# NeoDigito_Big_V2_1_PCBWay.net
KiCad netlist of a schematic drawn in EAGLE
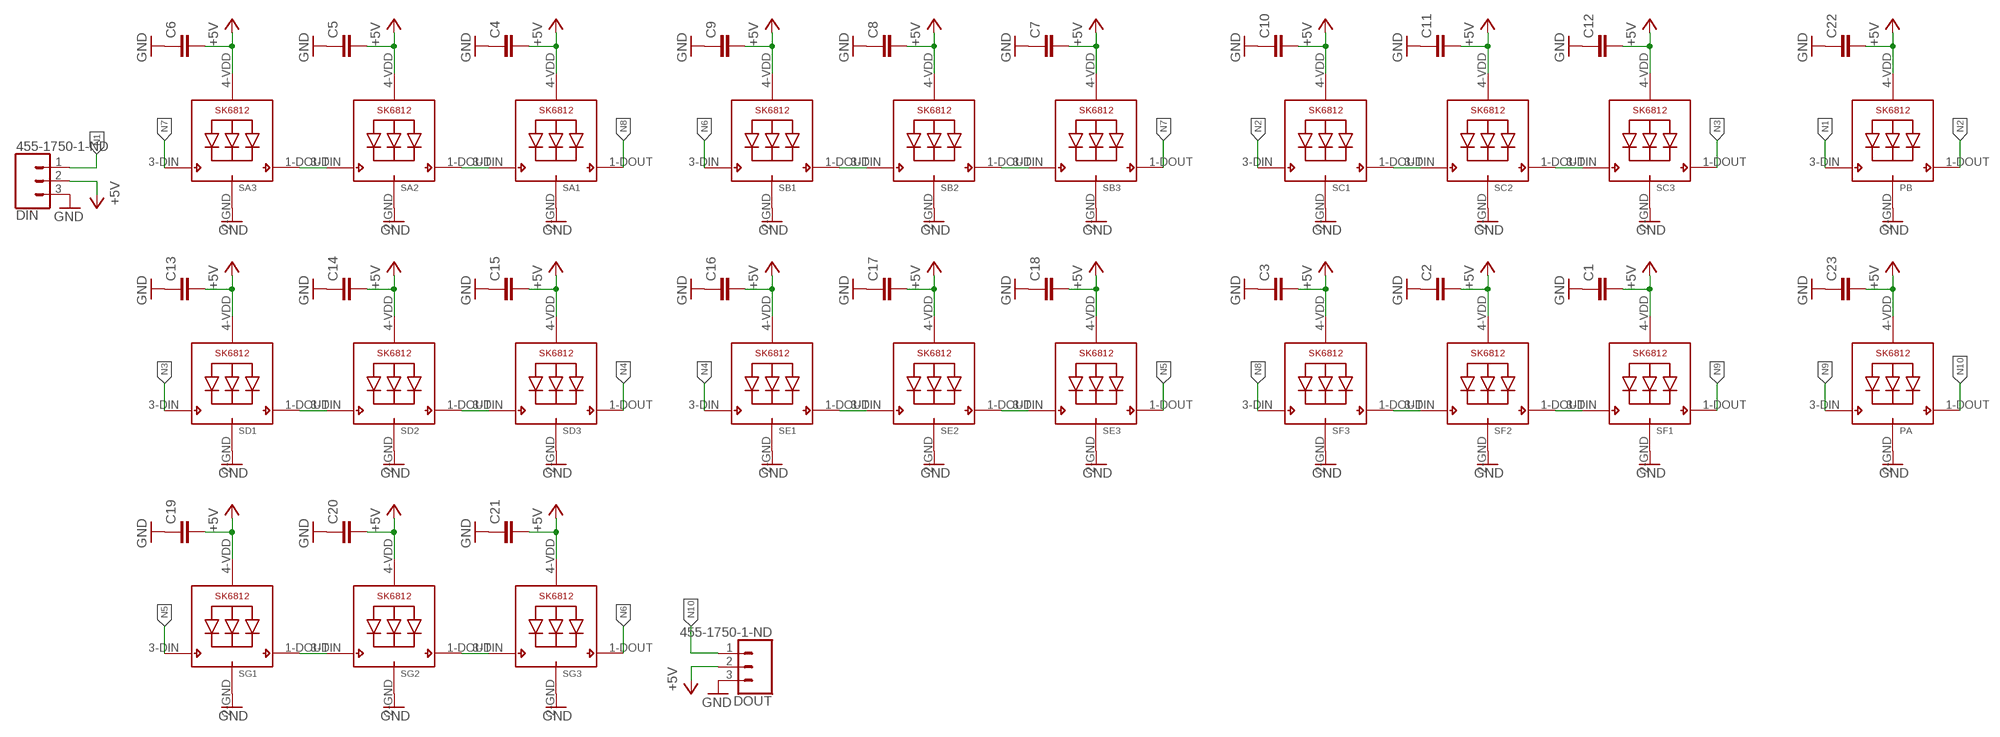
[diagram p0: schematic, sheet 1]

(export (version "E")
  (design (tool "Eeschema 10.0.6"))
  (components
    (comp (ref "C1")
      (value "C-EUC0805")
      (footprint "eagle-import:C0805")
      (libsource (lib "eagle-import") (part "C-EUC0805"))
    )
    (comp (ref "C2")
      (value "C-EUC0805")
      (footprint "eagle-import:C0805")
      (libsource (lib "eagle-import") (part "C-EUC0805"))
    )
    (comp (ref "C3")
      (value "C-EUC0805")
      (footprint "eagle-import:C0805")
      (libsource (lib "eagle-import") (part "C-EUC0805"))
    )
    (comp (ref "C4")
      (value "C-EUC0805")
      (footprint "eagle-import:C0805")
      (libsource (lib "eagle-import") (part "C-EUC0805"))
    )
    (comp (ref "C5")
      (value "C-EUC0805")
      (footprint "eagle-import:C0805")
      (libsource (lib "eagle-import") (part "C-EUC0805"))
    )
    (comp (ref "C6")
      (value "C-EUC0805")
      (footprint "eagle-import:C0805")
      (libsource (lib "eagle-import") (part "C-EUC0805"))
    )
    (comp (ref "C7")
      (value "C-EUC0805")
      (footprint "eagle-import:C0805")
      (libsource (lib "eagle-import") (part "C-EUC0805"))
    )
    (comp (ref "C8")
      (value "C-EUC0805")
      (footprint "eagle-import:C0805")
      (libsource (lib "eagle-import") (part "C-EUC0805"))
    )
    (comp (ref "C9")
      (value "C-EUC0805")
      (footprint "eagle-import:C0805")
      (libsource (lib "eagle-import") (part "C-EUC0805"))
    )
    (comp (ref "C10")
      (value "C-EUC0805")
      (footprint "eagle-import:C0805")
      (libsource (lib "eagle-import") (part "C-EUC0805"))
    )
    (comp (ref "C11")
      (value "C-EUC0805")
      (footprint "eagle-import:C0805")
      (libsource (lib "eagle-import") (part "C-EUC0805"))
    )
    (comp (ref "C12")
      (value "C-EUC0805")
      (footprint "eagle-import:C0805")
      (libsource (lib "eagle-import") (part "C-EUC0805"))
    )
    (comp (ref "C13")
      (value "C-EUC0805")
      (footprint "eagle-import:C0805")
      (libsource (lib "eagle-import") (part "C-EUC0805"))
    )
    (comp (ref "C14")
      (value "C-EUC0805")
      (footprint "eagle-import:C0805")
      (libsource (lib "eagle-import") (part "C-EUC0805"))
    )
    (comp (ref "C15")
      (value "C-EUC0805")
      (footprint "eagle-import:C0805")
      (libsource (lib "eagle-import") (part "C-EUC0805"))
    )
    (comp (ref "C16")
      (value "C-EUC0805")
      (footprint "eagle-import:C0805")
      (libsource (lib "eagle-import") (part "C-EUC0805"))
    )
    (comp (ref "C17")
      (value "C-EUC0805")
      (footprint "eagle-import:C0805")
      (libsource (lib "eagle-import") (part "C-EUC0805"))
    )
    (comp (ref "C18")
      (value "C-EUC0805")
      (footprint "eagle-import:C0805")
      (libsource (lib "eagle-import") (part "C-EUC0805"))
    )
    (comp (ref "C19")
      (value "C-EUC0805")
      (footprint "eagle-import:C0805")
      (libsource (lib "eagle-import") (part "C-EUC0805"))
    )
    (comp (ref "C20")
      (value "C-EUC0805")
      (footprint "eagle-import:C0805")
      (libsource (lib "eagle-import") (part "C-EUC0805"))
    )
    (comp (ref "C21")
      (value "C-EUC0805")
      (footprint "eagle-import:C0805")
      (libsource (lib "eagle-import") (part "C-EUC0805"))
    )
    (comp (ref "C22")
      (value "C-EUC0805")
      (footprint "eagle-import:C0805")
      (libsource (lib "eagle-import") (part "C-EUC0805"))
    )
    (comp (ref "C23")
      (value "C-EUC0805")
      (footprint "eagle-import:C0805")
      (libsource (lib "eagle-import") (part "C-EUC0805"))
    )
    (comp (ref "DIN")
      (value "455-1750-1-ND")
      (footprint "eagle-import:1X03")
      (libsource (lib "eagle-import") (part "CONN_03"))
    )
    (comp (ref "DOUT")
      (value "455-1750-1-ND")
      (footprint "eagle-import:1X03_NO_SILK")
      (libsource (lib "eagle-import") (part "CONN_031X03_NO_SILK"))
    )
    (comp (ref "PA")
      (value "SK6812_3535")
      (footprint "eagle-import:LED3535")
      (libsource (lib "eagle-import") (part "SK6812_3535"))
    )
    (comp (ref "PB")
      (value "SK6812_3535")
      (footprint "eagle-import:LED3535")
      (libsource (lib "eagle-import") (part "SK6812_3535"))
    )
    (comp (ref "SA1")
      (value "SK6812_3535")
      (footprint "eagle-import:LED3535")
      (libsource (lib "eagle-import") (part "SK6812_3535"))
    )
    (comp (ref "SA2")
      (value "SK6812_3535")
      (footprint "eagle-import:LED3535")
      (libsource (lib "eagle-import") (part "SK6812_3535"))
    )
    (comp (ref "SA3")
      (value "SK6812_3535")
      (footprint "eagle-import:LED3535")
      (libsource (lib "eagle-import") (part "SK6812_3535"))
    )
    (comp (ref "SB1")
      (value "SK6812_3535")
      (footprint "eagle-import:LED3535")
      (libsource (lib "eagle-import") (part "SK6812_3535"))
    )
    (comp (ref "SB2")
      (value "SK6812_3535")
      (footprint "eagle-import:LED3535")
      (libsource (lib "eagle-import") (part "SK6812_3535"))
    )
    (comp (ref "SB3")
      (value "SK6812_3535")
      (footprint "eagle-import:LED3535")
      (libsource (lib "eagle-import") (part "SK6812_3535"))
    )
    (comp (ref "SC1")
      (value "SK6812_3535")
      (footprint "eagle-import:LED3535")
      (libsource (lib "eagle-import") (part "SK6812_3535"))
    )
    (comp (ref "SC2")
      (value "SK6812_3535")
      (footprint "eagle-import:LED3535")
      (libsource (lib "eagle-import") (part "SK6812_3535"))
    )
    (comp (ref "SC3")
      (value "SK6812_3535")
      (footprint "eagle-import:LED3535")
      (libsource (lib "eagle-import") (part "SK6812_3535"))
    )
    (comp (ref "SD1")
      (value "SK6812_3535")
      (footprint "eagle-import:LED3535")
      (libsource (lib "eagle-import") (part "SK6812_3535"))
    )
    (comp (ref "SD2")
      (value "SK6812_3535")
      (footprint "eagle-import:LED3535")
      (libsource (lib "eagle-import") (part "SK6812_3535"))
    )
    (comp (ref "SD3")
      (value "SK6812_3535")
      (footprint "eagle-import:LED3535")
      (libsource (lib "eagle-import") (part "SK6812_3535"))
    )
    (comp (ref "SE1")
      (value "SK6812_3535")
      (footprint "eagle-import:LED3535")
      (libsource (lib "eagle-import") (part "SK6812_3535"))
    )
    (comp (ref "SE2")
      (value "SK6812_3535")
      (footprint "eagle-import:LED3535")
      (libsource (lib "eagle-import") (part "SK6812_3535"))
    )
    (comp (ref "SE3")
      (value "SK6812_3535")
      (footprint "eagle-import:LED3535")
      (libsource (lib "eagle-import") (part "SK6812_3535"))
    )
    (comp (ref "SF1")
      (value "SK6812_3535")
      (footprint "eagle-import:LED3535")
      (libsource (lib "eagle-import") (part "SK6812_3535"))
    )
    (comp (ref "SF2")
      (value "SK6812_3535")
      (footprint "eagle-import:LED3535")
      (libsource (lib "eagle-import") (part "SK6812_3535"))
    )
    (comp (ref "SF3")
      (value "SK6812_3535")
      (footprint "eagle-import:LED3535")
      (libsource (lib "eagle-import") (part "SK6812_3535"))
    )
    (comp (ref "SG1")
      (value "SK6812_3535")
      (footprint "eagle-import:LED3535")
      (libsource (lib "eagle-import") (part "SK6812_3535"))
    )
    (comp (ref "SG2")
      (value "SK6812_3535")
      (footprint "eagle-import:LED3535")
      (libsource (lib "eagle-import") (part "SK6812_3535"))
    )
    (comp (ref "SG3")
      (value "SK6812_3535")
      (footprint "eagle-import:LED3535")
      (libsource (lib "eagle-import") (part "SK6812_3535"))
    )
  )
  (nets
    (net (code "1") (name "+5V") (class "Default")
      (node (ref "C1") (pin "2") (pinfunction "2_2") (pintype "passive"))
      (node (ref "C10") (pin "2") (pinfunction "2_2") (pintype "passive"))
      (node (ref "C11") (pin "2") (pinfunction "2_2") (pintype "passive"))
      (node (ref "C12") (pin "2") (pinfunction "2_2") (pintype "passive"))
      (node (ref "C13") (pin "2") (pinfunction "2_2") (pintype "passive"))
      (node (ref "C14") (pin "2") (pinfunction "2_2") (pintype "passive"))
      (node (ref "C15") (pin "2") (pinfunction "2_2") (pintype "passive"))
      (node (ref "C16") (pin "2") (pinfunction "2_2") (pintype "passive"))
      (node (ref "C17") (pin "2") (pinfunction "2_2") (pintype "passive"))
      (node (ref "C18") (pin "2") (pinfunction "2_2") (pintype "passive"))
      (node (ref "C19") (pin "2") (pinfunction "2_2") (pintype "passive"))
      (node (ref "C2") (pin "2") (pinfunction "2_2") (pintype "passive"))
      (node (ref "C20") (pin "2") (pinfunction "2_2") (pintype "passive"))
      (node (ref "C21") (pin "2") (pinfunction "2_2") (pintype "passive"))
      (node (ref "C22") (pin "2") (pinfunction "2_2") (pintype "passive"))
      (node (ref "C23") (pin "2") (pinfunction "2_2") (pintype "passive"))
      (node (ref "C3") (pin "2") (pinfunction "2_2") (pintype "passive"))
      (node (ref "C4") (pin "2") (pinfunction "2_2") (pintype "passive"))
      (node (ref "C5") (pin "2") (pinfunction "2_2") (pintype "passive"))
      (node (ref "C6") (pin "2") (pinfunction "2_2") (pintype "passive"))
      (node (ref "C7") (pin "2") (pinfunction "2_2") (pintype "passive"))
      (node (ref "C8") (pin "2") (pinfunction "2_2") (pintype "passive"))
      (node (ref "C9") (pin "2") (pinfunction "2_2") (pintype "passive"))
      (node (ref "DIN") (pin "2") (pinfunction "2_2") (pintype "passive"))
      (node (ref "DOUT") (pin "2") (pinfunction "2_2") (pintype "passive"))
      (node (ref "PA") (pin "4-VDD") (pinfunction "VDD_4-VDD") (pintype "power_in"))
      (node (ref "PB") (pin "4-VDD") (pinfunction "VDD_4-VDD") (pintype "power_in"))
      (node (ref "SA1") (pin "4-VDD") (pinfunction "VDD_4-VDD") (pintype "power_in"))
      (node (ref "SA2") (pin "4-VDD") (pinfunction "VDD_4-VDD") (pintype "power_in"))
      (node (ref "SA3") (pin "4-VDD") (pinfunction "VDD_4-VDD") (pintype "power_in"))
      (node (ref "SB1") (pin "4-VDD") (pinfunction "VDD_4-VDD") (pintype "power_in"))
      (node (ref "SB2") (pin "4-VDD") (pinfunction "VDD_4-VDD") (pintype "power_in"))
      (node (ref "SB3") (pin "4-VDD") (pinfunction "VDD_4-VDD") (pintype "power_in"))
      (node (ref "SC1") (pin "4-VDD") (pinfunction "VDD_4-VDD") (pintype "power_in"))
      (node (ref "SC2") (pin "4-VDD") (pinfunction "VDD_4-VDD") (pintype "power_in"))
      (node (ref "SC3") (pin "4-VDD") (pinfunction "VDD_4-VDD") (pintype "power_in"))
      (node (ref "SD1") (pin "4-VDD") (pinfunction "VDD_4-VDD") (pintype "power_in"))
      (node (ref "SD2") (pin "4-VDD") (pinfunction "VDD_4-VDD") (pintype "power_in"))
      (node (ref "SD3") (pin "4-VDD") (pinfunction "VDD_4-VDD") (pintype "power_in"))
      (node (ref "SE1") (pin "4-VDD") (pinfunction "VDD_4-VDD") (pintype "power_in"))
      (node (ref "SE2") (pin "4-VDD") (pinfunction "VDD_4-VDD") (pintype "power_in"))
      (node (ref "SE3") (pin "4-VDD") (pinfunction "VDD_4-VDD") (pintype "power_in"))
      (node (ref "SF1") (pin "4-VDD") (pinfunction "VDD_4-VDD") (pintype "power_in"))
      (node (ref "SF2") (pin "4-VDD") (pinfunction "VDD_4-VDD") (pintype "power_in"))
      (node (ref "SF3") (pin "4-VDD") (pinfunction "VDD_4-VDD") (pintype "power_in"))
      (node (ref "SG1") (pin "4-VDD") (pinfunction "VDD_4-VDD") (pintype "power_in"))
      (node (ref "SG2") (pin "4-VDD") (pinfunction "VDD_4-VDD") (pintype "power_in"))
      (node (ref "SG3") (pin "4-VDD") (pinfunction "VDD_4-VDD") (pintype "power_in"))
    )
    (net (code "2") (name "GND") (class "Default")
      (node (ref "C1") (pin "1") (pinfunction "1_1") (pintype "passive"))
      (node (ref "C10") (pin "1") (pinfunction "1_1") (pintype "passive"))
      (node (ref "C11") (pin "1") (pinfunction "1_1") (pintype "passive"))
      (node (ref "C12") (pin "1") (pinfunction "1_1") (pintype "passive"))
      (node (ref "C13") (pin "1") (pinfunction "1_1") (pintype "passive"))
      (node (ref "C14") (pin "1") (pinfunction "1_1") (pintype "passive"))
      (node (ref "C15") (pin "1") (pinfunction "1_1") (pintype "passive"))
      (node (ref "C16") (pin "1") (pinfunction "1_1") (pintype "passive"))
      (node (ref "C17") (pin "1") (pinfunction "1_1") (pintype "passive"))
      (node (ref "C18") (pin "1") (pinfunction "1_1") (pintype "passive"))
      (node (ref "C19") (pin "1") (pinfunction "1_1") (pintype "passive"))
      (node (ref "C2") (pin "1") (pinfunction "1_1") (pintype "passive"))
      (node (ref "C20") (pin "1") (pinfunction "1_1") (pintype "passive"))
      (node (ref "C21") (pin "1") (pinfunction "1_1") (pintype "passive"))
      (node (ref "C22") (pin "1") (pinfunction "1_1") (pintype "passive"))
      (node (ref "C23") (pin "1") (pinfunction "1_1") (pintype "passive"))
      (node (ref "C3") (pin "1") (pinfunction "1_1") (pintype "passive"))
      (node (ref "C4") (pin "1") (pinfunction "1_1") (pintype "passive"))
      (node (ref "C5") (pin "1") (pinfunction "1_1") (pintype "passive"))
      (node (ref "C6") (pin "1") (pinfunction "1_1") (pintype "passive"))
      (node (ref "C7") (pin "1") (pinfunction "1_1") (pintype "passive"))
      (node (ref "C8") (pin "1") (pinfunction "1_1") (pintype "passive"))
      (node (ref "C9") (pin "1") (pinfunction "1_1") (pintype "passive"))
      (node (ref "DIN") (pin "3") (pinfunction "3_3") (pintype "passive"))
      (node (ref "DOUT") (pin "3") (pinfunction "3_3") (pintype "passive"))
      (node (ref "PA") (pin "2-GND") (pinfunction "GND_2-GND") (pintype "power_in"))
      (node (ref "PB") (pin "2-GND") (pinfunction "GND_2-GND") (pintype "power_in"))
      (node (ref "SA1") (pin "2-GND") (pinfunction "GND_2-GND") (pintype "power_in"))
      (node (ref "SA2") (pin "2-GND") (pinfunction "GND_2-GND") (pintype "power_in"))
      (node (ref "SA3") (pin "2-GND") (pinfunction "GND_2-GND") (pintype "power_in"))
      (node (ref "SB1") (pin "2-GND") (pinfunction "GND_2-GND") (pintype "power_in"))
      (node (ref "SB2") (pin "2-GND") (pinfunction "GND_2-GND") (pintype "power_in"))
      (node (ref "SB3") (pin "2-GND") (pinfunction "GND_2-GND") (pintype "power_in"))
      (node (ref "SC1") (pin "2-GND") (pinfunction "GND_2-GND") (pintype "power_in"))
      (node (ref "SC2") (pin "2-GND") (pinfunction "GND_2-GND") (pintype "power_in"))
      (node (ref "SC3") (pin "2-GND") (pinfunction "GND_2-GND") (pintype "power_in"))
      (node (ref "SD1") (pin "2-GND") (pinfunction "GND_2-GND") (pintype "power_in"))
      (node (ref "SD2") (pin "2-GND") (pinfunction "GND_2-GND") (pintype "power_in"))
      (node (ref "SD3") (pin "2-GND") (pinfunction "GND_2-GND") (pintype "power_in"))
      (node (ref "SE1") (pin "2-GND") (pinfunction "GND_2-GND") (pintype "power_in"))
      (node (ref "SE2") (pin "2-GND") (pinfunction "GND_2-GND") (pintype "power_in"))
      (node (ref "SE3") (pin "2-GND") (pinfunction "GND_2-GND") (pintype "power_in"))
      (node (ref "SF1") (pin "2-GND") (pinfunction "GND_2-GND") (pintype "power_in"))
      (node (ref "SF2") (pin "2-GND") (pinfunction "GND_2-GND") (pintype "power_in"))
      (node (ref "SF3") (pin "2-GND") (pinfunction "GND_2-GND") (pintype "power_in"))
      (node (ref "SG1") (pin "2-GND") (pinfunction "GND_2-GND") (pintype "power_in"))
      (node (ref "SG2") (pin "2-GND") (pinfunction "GND_2-GND") (pintype "power_in"))
      (node (ref "SG3") (pin "2-GND") (pinfunction "GND_2-GND") (pintype "power_in"))
    )
    (net (code "3") (name "N1") (class "Default")
      (node (ref "DIN") (pin "1") (pinfunction "1_1") (pintype "passive"))
      (node (ref "PB") (pin "3-DIN") (pinfunction "DI_3-DIN") (pintype "input"))
    )
    (net (code "4") (name "N2") (class "Default")
      (node (ref "PB") (pin "1-DOUT") (pinfunction "DO_1-DOUT") (pintype "output"))
      (node (ref "SC1") (pin "3-DIN") (pinfunction "DI_3-DIN") (pintype "input"))
    )
    (net (code "5") (name "N3") (class "Default")
      (node (ref "SC3") (pin "1-DOUT") (pinfunction "DO_1-DOUT") (pintype "output"))
      (node (ref "SD1") (pin "3-DIN") (pinfunction "DI_3-DIN") (pintype "input"))
    )
    (net (code "6") (name "N4") (class "Default")
      (node (ref "SD3") (pin "1-DOUT") (pinfunction "DO_1-DOUT") (pintype "output"))
      (node (ref "SE1") (pin "3-DIN") (pinfunction "DI_3-DIN") (pintype "input"))
    )
    (net (code "7") (name "N5") (class "Default")
      (node (ref "SE3") (pin "1-DOUT") (pinfunction "DO_1-DOUT") (pintype "output"))
      (node (ref "SG1") (pin "3-DIN") (pinfunction "DI_3-DIN") (pintype "input"))
    )
    (net (code "8") (name "N6") (class "Default")
      (node (ref "SB1") (pin "3-DIN") (pinfunction "DI_3-DIN") (pintype "input"))
      (node (ref "SG3") (pin "1-DOUT") (pinfunction "DO_1-DOUT") (pintype "output"))
    )
    (net (code "9") (name "N7") (class "Default")
      (node (ref "SA3") (pin "3-DIN") (pinfunction "DI_3-DIN") (pintype "input"))
      (node (ref "SB3") (pin "1-DOUT") (pinfunction "DO_1-DOUT") (pintype "output"))
    )
    (net (code "10") (name "N8") (class "Default")
      (node (ref "SA1") (pin "1-DOUT") (pinfunction "DO_1-DOUT") (pintype "output"))
      (node (ref "SF3") (pin "3-DIN") (pinfunction "DI_3-DIN") (pintype "input"))
    )
    (net (code "11") (name "N9") (class "Default")
      (node (ref "PA") (pin "3-DIN") (pinfunction "DI_3-DIN") (pintype "input"))
      (node (ref "SF1") (pin "1-DOUT") (pinfunction "DO_1-DOUT") (pintype "output"))
    )
    (net (code "12") (name "N10") (class "Default")
      (node (ref "DOUT") (pin "1") (pinfunction "1_1") (pintype "passive"))
      (node (ref "PA") (pin "1-DOUT") (pinfunction "DO_1-DOUT") (pintype "output"))
    )
    (net (code "13") (name "Net-(SA1-DI)") (class "Default")
      (node (ref "SA1") (pin "3-DIN") (pinfunction "DI_3-DIN") (pintype "input"))
      (node (ref "SA2") (pin "1-DOUT") (pinfunction "DO_1-DOUT") (pintype "output"))
    )
    (net (code "14") (name "Net-(SA2-DI)") (class "Default")
      (node (ref "SA2") (pin "3-DIN") (pinfunction "DI_3-DIN") (pintype "input"))
      (node (ref "SA3") (pin "1-DOUT") (pinfunction "DO_1-DOUT") (pintype "output"))
    )
    (net (code "15") (name "Net-(SB1-DO)") (class "Default")
      (node (ref "SB1") (pin "1-DOUT") (pinfunction "DO_1-DOUT") (pintype "output"))
      (node (ref "SB2") (pin "3-DIN") (pinfunction "DI_3-DIN") (pintype "input"))
    )
    (net (code "16") (name "Net-(SB2-DO)") (class "Default")
      (node (ref "SB2") (pin "1-DOUT") (pinfunction "DO_1-DOUT") (pintype "output"))
      (node (ref "SB3") (pin "3-DIN") (pinfunction "DI_3-DIN") (pintype "input"))
    )
    (net (code "17") (name "Net-(SC1-DO)") (class "Default")
      (node (ref "SC1") (pin "1-DOUT") (pinfunction "DO_1-DOUT") (pintype "output"))
      (node (ref "SC2") (pin "3-DIN") (pinfunction "DI_3-DIN") (pintype "input"))
    )
    (net (code "18") (name "Net-(SC2-DO)") (class "Default")
      (node (ref "SC2") (pin "1-DOUT") (pinfunction "DO_1-DOUT") (pintype "output"))
      (node (ref "SC3") (pin "3-DIN") (pinfunction "DI_3-DIN") (pintype "input"))
    )
    (net (code "19") (name "Net-(SD1-DO)") (class "Default")
      (node (ref "SD1") (pin "1-DOUT") (pinfunction "DO_1-DOUT") (pintype "output"))
      (node (ref "SD2") (pin "3-DIN") (pinfunction "DI_3-DIN") (pintype "input"))
    )
    (net (code "20") (name "Net-(SD2-DO)") (class "Default")
      (node (ref "SD2") (pin "1-DOUT") (pinfunction "DO_1-DOUT") (pintype "output"))
      (node (ref "SD3") (pin "3-DIN") (pinfunction "DI_3-DIN") (pintype "input"))
    )
    (net (code "21") (name "Net-(SE1-DO)") (class "Default")
      (node (ref "SE1") (pin "1-DOUT") (pinfunction "DO_1-DOUT") (pintype "output"))
      (node (ref "SE2") (pin "3-DIN") (pinfunction "DI_3-DIN") (pintype "input"))
    )
    (net (code "22") (name "Net-(SE2-DO)") (class "Default")
      (node (ref "SE2") (pin "1-DOUT") (pinfunction "DO_1-DOUT") (pintype "output"))
      (node (ref "SE3") (pin "3-DIN") (pinfunction "DI_3-DIN") (pintype "input"))
    )
    (net (code "23") (name "Net-(SF1-DI)") (class "Default")
      (node (ref "SF1") (pin "3-DIN") (pinfunction "DI_3-DIN") (pintype "input"))
      (node (ref "SF2") (pin "1-DOUT") (pinfunction "DO_1-DOUT") (pintype "output"))
    )
    (net (code "24") (name "Net-(SF2-DI)") (class "Default")
      (node (ref "SF2") (pin "3-DIN") (pinfunction "DI_3-DIN") (pintype "input"))
      (node (ref "SF3") (pin "1-DOUT") (pinfunction "DO_1-DOUT") (pintype "output"))
    )
    (net (code "25") (name "Net-(SG1-DO)") (class "Default")
      (node (ref "SG1") (pin "1-DOUT") (pinfunction "DO_1-DOUT") (pintype "output"))
      (node (ref "SG2") (pin "3-DIN") (pinfunction "DI_3-DIN") (pintype "input"))
    )
    (net (code "26") (name "Net-(SG2-DO)") (class "Default")
      (node (ref "SG2") (pin "1-DOUT") (pinfunction "DO_1-DOUT") (pintype "output"))
      (node (ref "SG3") (pin "3-DIN") (pinfunction "DI_3-DIN") (pintype "input"))
    )
  )
)
